# LED1.net
KiCad netlist of a schematic drawn in Altium Designer
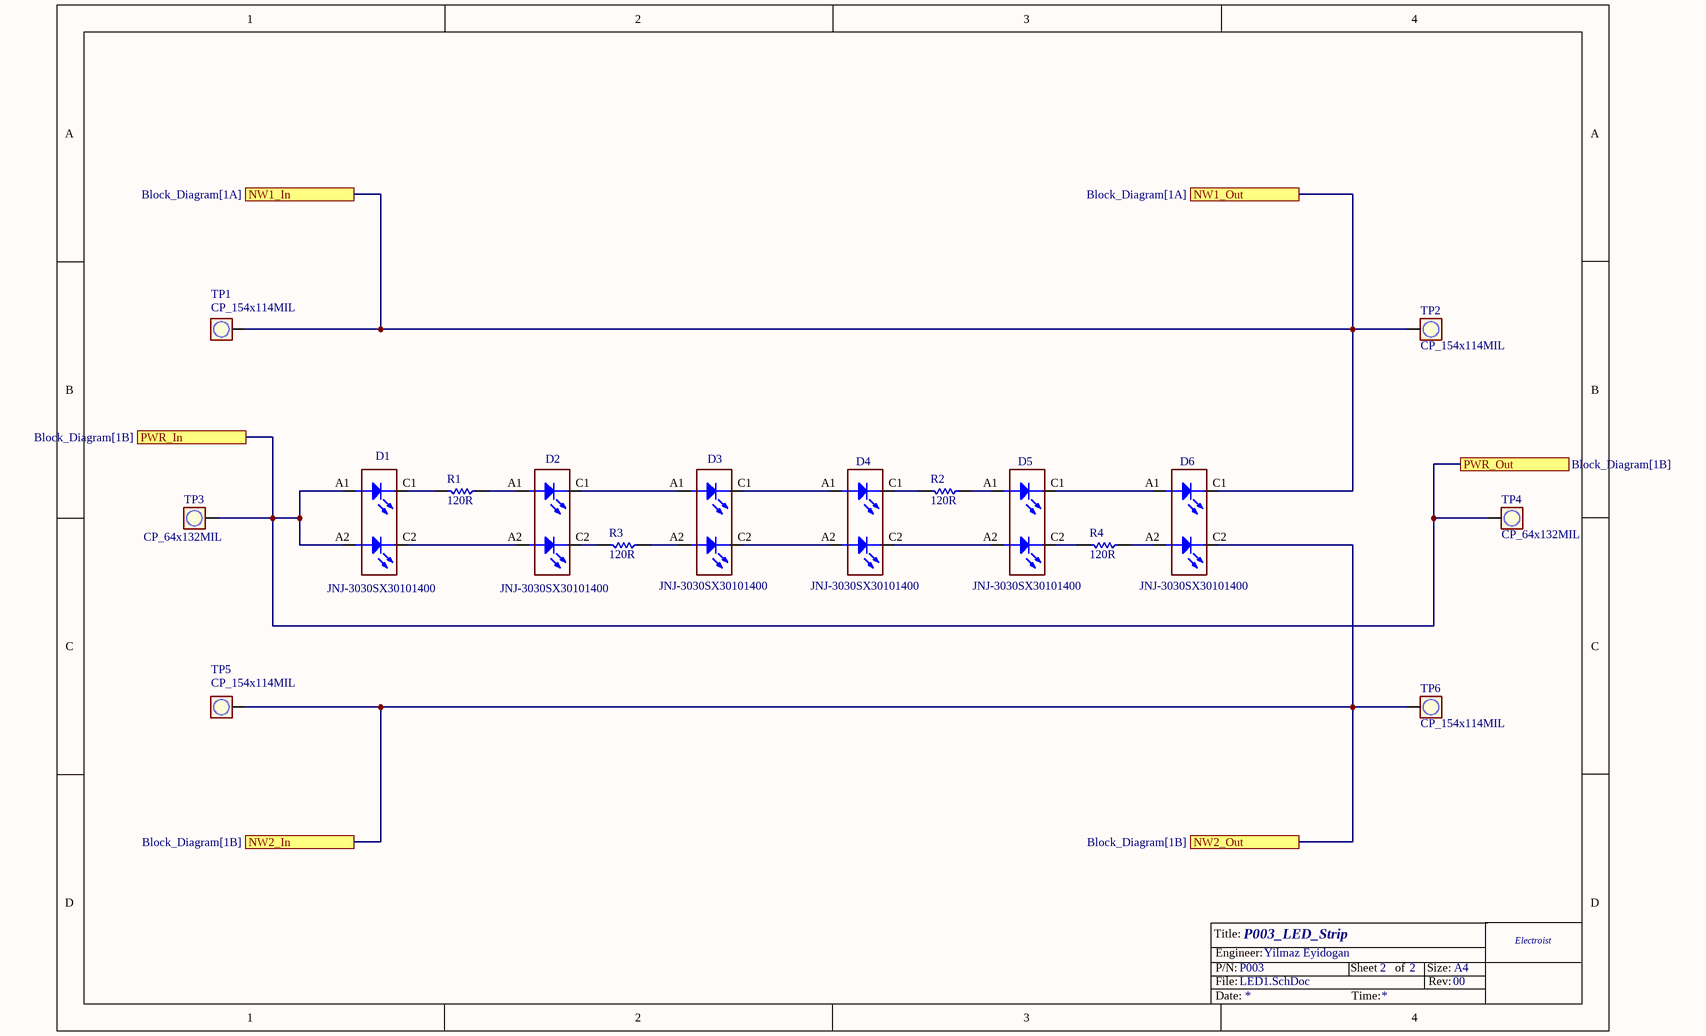
[diagram p0: LED1.SchDoc]

(export (version "E")
  (design (tool "Eeschema 10.0.6"))
  (components
    (comp (ref "D1")
      (value "JNJ-3030SX30101400")
      (footprint "LED_3030_4P_1")
      (description "Dual LED, 3030 4 pin package")
      (fields
        (field (name "VOLTAGE") "3.1V")
        (field (name "MANUFACTURER") "JNJ Optoelectronics")
        (field (name "PUBLISHER") "YE")
      )
      (libsource (lib "Database_Libs") (part "DSP_LED_Dual"))
    )
    (comp (ref "D2")
      (value "JNJ-3030SX30101400")
      (footprint "LED_3030_4P_1")
      (description "Dual LED, 3030 4 pin package")
      (fields
        (field (name "VOLTAGE") "3.1V")
        (field (name "MANUFACTURER") "JNJ Optoelectronics")
        (field (name "PUBLISHER") "YE")
      )
      (libsource (lib "Database_Libs") (part "DSP_LED_Dual"))
    )
    (comp (ref "D3")
      (value "JNJ-3030SX30101400")
      (footprint "LED_3030_4P_1")
      (description "Dual LED, 3030 4 pin package")
      (fields
        (field (name "VOLTAGE") "3.1V")
        (field (name "MANUFACTURER") "JNJ Optoelectronics")
        (field (name "PUBLISHER") "YE")
      )
      (libsource (lib "Database_Libs") (part "DSP_LED_Dual"))
    )
    (comp (ref "D4")
      (value "JNJ-3030SX30101400")
      (footprint "LED_3030_4P_1")
      (description "Dual LED, 3030 4 pin package")
      (fields
        (field (name "VOLTAGE") "3.1V")
        (field (name "MANUFACTURER") "JNJ Optoelectronics")
        (field (name "PUBLISHER") "YE")
      )
      (libsource (lib "Database_Libs") (part "DSP_LED_Dual"))
    )
    (comp (ref "D5")
      (value "JNJ-3030SX30101400")
      (footprint "LED_3030_4P_1")
      (description "Dual LED, 3030 4 pin package")
      (fields
        (field (name "VOLTAGE") "3.1V")
        (field (name "MANUFACTURER") "JNJ Optoelectronics")
        (field (name "PUBLISHER") "YE")
      )
      (libsource (lib "Database_Libs") (part "DSP_LED_Dual"))
    )
    (comp (ref "D6")
      (value "JNJ-3030SX30101400")
      (footprint "LED_3030_4P_1")
      (description "Dual LED, 3030 4 pin package")
      (fields
        (field (name "VOLTAGE") "3.1V")
        (field (name "MANUFACTURER") "JNJ Optoelectronics")
        (field (name "PUBLISHER") "YE")
      )
      (libsource (lib "Database_Libs") (part "DSP_LED_Dual"))
    )
    (comp (ref "R1")
      (value "120R")
      (footprint "RES_CHIP_3216[1206]_N")
      (description "120 ohm, 1206, 250 mW, 200 V, %10")
      (fields
        (field (name "PART NUMBER") "120R_1206")
        (field (name "VOLTAGE") "200V")
        (field (name "PUBLISHER") "YE")
      )
      (libsource (lib "Database_Libs") (part "RES_R"))
    )
    (comp (ref "R2")
      (value "120R")
      (footprint "RES_CHIP_3216[1206]_N")
      (description "120 ohm, 1206, 250 mW, 200 V, %10")
      (fields
        (field (name "PART NUMBER") "120R_1206")
        (field (name "VOLTAGE") "200V")
        (field (name "PUBLISHER") "YE")
      )
      (libsource (lib "Database_Libs") (part "RES_R"))
    )
    (comp (ref "R3")
      (value "120R")
      (footprint "RES_CHIP_3216[1206]_N")
      (description "120 ohm, 1206, 250 mW, 200 V, %10")
      (fields
        (field (name "PART NUMBER") "120R_1206")
        (field (name "VOLTAGE") "200V")
        (field (name "PUBLISHER") "YE")
      )
      (libsource (lib "Database_Libs") (part "RES_R"))
    )
    (comp (ref "R4")
      (value "120R")
      (footprint "RES_CHIP_3216[1206]_N")
      (description "120 ohm, 1206, 250 mW, 200 V, %10")
      (fields
        (field (name "PART NUMBER") "120R_1206")
        (field (name "VOLTAGE") "200V")
        (field (name "PUBLISHER") "YE")
      )
      (libsource (lib "Database_Libs") (part "RES_R"))
    )
    (comp (ref "TP1")
      (value "CP_154x114MIL")
      (footprint "TST_CP_154x114MIL")
      (description "no via")
      (fields (field (name "PUBLISHER") "YE"))
      (libsource (lib "Database_Libs") (part "TST_TP_1"))
    )
    (comp (ref "TP2")
      (value "CP_154x114MIL")
      (footprint "TST_CP_154x114MIL")
      (description "no via")
      (fields (field (name "PUBLISHER") "YE"))
      (libsource (lib "") (part "TST_TP_1_1"))
    )
    (comp (ref "TP3")
      (value "CP_64x132MIL")
      (footprint "TST_CP_64x132MIL_1")
      (description "includes 3 vias")
      (fields (field (name "PUBLISHER") "YE"))
      (libsource (lib "Database_Libs") (part "TST_TP_1"))
    )
    (comp (ref "TP4")
      (value "CP_64x132MIL")
      (footprint "TST_CP_64x132MIL_1")
      (description "includes 3 vias")
      (fields (field (name "PUBLISHER") "YE"))
      (libsource (lib "") (part "TST_TP_1_1"))
    )
    (comp (ref "TP5")
      (value "CP_154x114MIL")
      (footprint "TST_CP_154x114MIL")
      (description "no via")
      (fields (field (name "PUBLISHER") "YE"))
      (libsource (lib "Database_Libs") (part "TST_TP_1"))
    )
    (comp (ref "TP6")
      (value "CP_154x114MIL")
      (footprint "TST_CP_154x114MIL")
      (description "no via")
      (fields (field (name "PUBLISHER") "YE"))
      (libsource (lib "") (part "TST_TP_1_1"))
    )
  )
  (nets
    (net (code "1") (name "/NW1_In") (class "Default")
      (node (ref "D6") (pin "C1") (pinfunction "C1_C1") (pintype "passive"))
      (node (ref "TP1") (pin "1") (pinfunction "1_1") (pintype "passive"))
      (node (ref "TP2") (pin "1") (pinfunction "1_1") (pintype "passive"))
    )
    (net (code "2") (name "/NW2_In") (class "Default")
      (node (ref "D6") (pin "C2") (pinfunction "C2_C2") (pintype "passive"))
      (node (ref "TP5") (pin "1") (pinfunction "1_1") (pintype "passive"))
      (node (ref "TP6") (pin "1") (pinfunction "1_1") (pintype "passive"))
    )
    (net (code "3") (name "/PWR_In") (class "Default")
      (node (ref "D1") (pin "A1") (pinfunction "A1_A1") (pintype "passive"))
      (node (ref "D1") (pin "A2") (pinfunction "A2_A2") (pintype "passive"))
      (node (ref "TP3") (pin "1") (pinfunction "1_1") (pintype "passive"))
      (node (ref "TP4") (pin "1") (pinfunction "1_1") (pintype "passive"))
    )
    (net (code "4") (name "Net-(D1-PadC1)") (class "Default")
      (node (ref "D1") (pin "C1") (pinfunction "C1_C1") (pintype "passive"))
      (node (ref "R1") (pin "2") (pinfunction "2_2") (pintype "passive"))
    )
    (net (code "5") (name "Net-(D1-PadC2)") (class "Default")
      (node (ref "D1") (pin "C2") (pinfunction "C2_C2") (pintype "passive"))
      (node (ref "D2") (pin "A2") (pinfunction "A2_A2") (pintype "passive"))
    )
    (net (code "6") (name "Net-(D2-PadA1)") (class "Default")
      (node (ref "D2") (pin "A1") (pinfunction "A1_A1") (pintype "passive"))
      (node (ref "R1") (pin "1") (pinfunction "1_1") (pintype "passive"))
    )
    (net (code "7") (name "Net-(D2-PadC1)") (class "Default")
      (node (ref "D2") (pin "C1") (pinfunction "C1_C1") (pintype "passive"))
      (node (ref "D3") (pin "A1") (pinfunction "A1_A1") (pintype "passive"))
    )
    (net (code "8") (name "Net-(D2-PadC2)") (class "Default")
      (node (ref "D2") (pin "C2") (pinfunction "C2_C2") (pintype "passive"))
      (node (ref "R3") (pin "2") (pinfunction "2_2") (pintype "passive"))
    )
    (net (code "9") (name "Net-(D3-PadA2)") (class "Default")
      (node (ref "D3") (pin "A2") (pinfunction "A2_A2") (pintype "passive"))
      (node (ref "R3") (pin "1") (pinfunction "1_1") (pintype "passive"))
    )
    (net (code "10") (name "Net-(D3-PadC1)") (class "Default")
      (node (ref "D3") (pin "C1") (pinfunction "C1_C1") (pintype "passive"))
      (node (ref "D4") (pin "A1") (pinfunction "A1_A1") (pintype "passive"))
    )
    (net (code "11") (name "Net-(D3-PadC2)") (class "Default")
      (node (ref "D3") (pin "C2") (pinfunction "C2_C2") (pintype "passive"))
      (node (ref "D4") (pin "A2") (pinfunction "A2_A2") (pintype "passive"))
    )
    (net (code "12") (name "Net-(D4-PadC1)") (class "Default")
      (node (ref "D4") (pin "C1") (pinfunction "C1_C1") (pintype "passive"))
      (node (ref "R2") (pin "2") (pinfunction "2_2") (pintype "passive"))
    )
    (net (code "13") (name "Net-(D4-PadC2)") (class "Default")
      (node (ref "D4") (pin "C2") (pinfunction "C2_C2") (pintype "passive"))
      (node (ref "D5") (pin "A2") (pinfunction "A2_A2") (pintype "passive"))
    )
    (net (code "14") (name "Net-(D5-PadA1)") (class "Default")
      (node (ref "D5") (pin "A1") (pinfunction "A1_A1") (pintype "passive"))
      (node (ref "R2") (pin "1") (pinfunction "1_1") (pintype "passive"))
    )
    (net (code "15") (name "Net-(D5-PadC1)") (class "Default")
      (node (ref "D5") (pin "C1") (pinfunction "C1_C1") (pintype "passive"))
      (node (ref "D6") (pin "A1") (pinfunction "A1_A1") (pintype "passive"))
    )
    (net (code "16") (name "Net-(D5-PadC2)") (class "Default")
      (node (ref "D5") (pin "C2") (pinfunction "C2_C2") (pintype "passive"))
      (node (ref "R4") (pin "2") (pinfunction "2_2") (pintype "passive"))
    )
    (net (code "17") (name "Net-(D6-PadA2)") (class "Default")
      (node (ref "D6") (pin "A2") (pinfunction "A2_A2") (pintype "passive"))
      (node (ref "R4") (pin "1") (pinfunction "1_1") (pintype "passive"))
    )
  )
)
